# tb-light.net
KiCad netlist of a schematic drawn in EAGLE
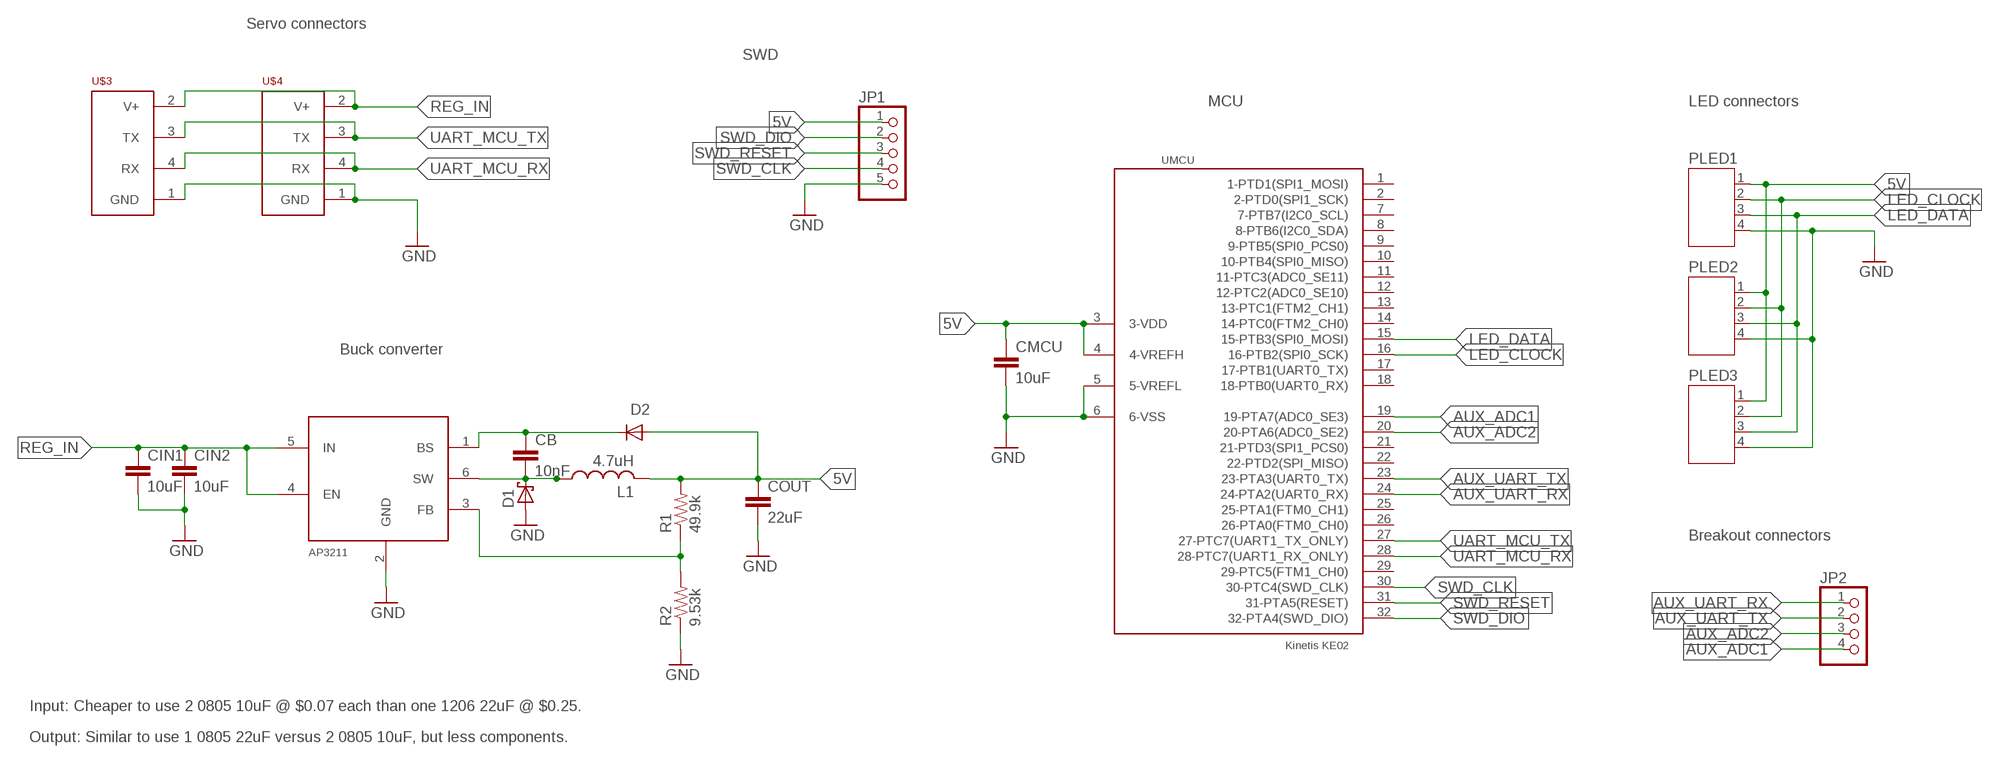
[diagram p0: schematic, sheet 1]

(export (version "E")
  (design (tool "Eeschema 10.0.6"))
  (components
    (comp (ref "CB")
      (value "10nF")
      (footprint "eagle-import:C0805")
      (libsource (lib "eagle-import") (part "CAPACITOR_0805"))
    )
    (comp (ref "CIN1")
      (value "10uF")
      (footprint "eagle-import:C0805")
      (libsource (lib "eagle-import") (part "CAPACITOR_0805"))
    )
    (comp (ref "CIN2")
      (value "10uF")
      (footprint "eagle-import:C0805")
      (libsource (lib "eagle-import") (part "CAPACITOR_0805"))
    )
    (comp (ref "CMCU")
      (value "10uF")
      (footprint "eagle-import:C0805")
      (libsource (lib "eagle-import") (part "CAPACITOR_0805"))
    )
    (comp (ref "COUT")
      (value "22uF")
      (footprint "eagle-import:C0805")
      (libsource (lib "eagle-import") (part "CAPACITOR_0805"))
    )
    (comp (ref "D1")
      (value "SCHOTTKY")
      (footprint "eagle-import:SOD-123FL")
      (libsource (lib "eagle-import") (part "SCHOTTKY"))
    )
    (comp (ref "D2")
      (value "SMALL-SIGNALSOD-123")
      (footprint "eagle-import:SOD-123")
      (libsource (lib "eagle-import") (part "SMALL-SIGNALSOD-123"))
    )
    (comp (ref "JP1")
      (value "PINHD-1X5")
      (footprint "eagle-import:1X05")
      (libsource (lib "eagle-import") (part "PINHD-1X5"))
    )
    (comp (ref "JP2")
      (value "PINHD-1X4")
      (footprint "eagle-import:1X04")
      (libsource (lib "eagle-import") (part "PINHD-1X4"))
    )
    (comp (ref "L1")
      (value "4.7uH")
      (footprint "eagle-import:L_NR6028")
      (libsource (lib "eagle-import") (part "INDUCTOR"))
    )
    (comp (ref "PLED1")
      (value "JST-PH4")
      (footprint "eagle-import:JST-PH4")
      (libsource (lib "eagle-import") (part "JST-PH4"))
    )
    (comp (ref "PLED2")
      (value "JST-PH4")
      (footprint "eagle-import:JST-PH4")
      (libsource (lib "eagle-import") (part "JST-PH4"))
    )
    (comp (ref "PLED3")
      (value "JST-PH4")
      (footprint "eagle-import:JST-PH4")
      (libsource (lib "eagle-import") (part "JST-PH4"))
    )
    (comp (ref "R1")
      (value "49.9k")
      (footprint "eagle-import:R0805")
      (libsource (lib "eagle-import") (part "RESISTOR_0805"))
    )
    (comp (ref "R2")
      (value "9.53k")
      (footprint "eagle-import:R0805")
      (libsource (lib "eagle-import") (part "RESISTOR_0805"))
    )
    (comp (ref "U$3")
      (value "SERVO-CONNVERT")
      (footprint "eagle-import:TE-AMP-4PIN")
      (libsource (lib "eagle-import") (part "SERVO-CONNVERT"))
    )
    (comp (ref "U$4")
      (value "SERVO-CONNVERT")
      (footprint "eagle-import:TE-AMP-4PIN")
      (libsource (lib "eagle-import") (part "SERVO-CONNVERT"))
    )
    (comp (ref "UMCU")
      (value "KE02")
      (footprint "eagle-import:TQFP32-08")
      (libsource (lib "eagle-import") (part "KE02"))
    )
    (comp (ref "UREG")
      (value "AP3211")
      (footprint "eagle-import:SOT23-6")
      (libsource (lib "eagle-import") (part "AP3211"))
    )
  )
  (nets
    (net (code "1") (name "5V") (class "Default")
      (node (ref "CMCU") (pin "1") (pinfunction "1_1") (pintype "passive"))
      (node (ref "COUT") (pin "1") (pinfunction "1_1") (pintype "passive"))
      (node (ref "D2") (pin "A") (pinfunction "A_A") (pintype "passive"))
      (node (ref "JP1") (pin "1") (pinfunction "1_1") (pintype "passive"))
      (node (ref "L1") (pin "P$2") (pinfunction "2_P$2") (pintype "passive"))
      (node (ref "PLED1") (pin "1") (pinfunction "1_1") (pintype "passive"))
      (node (ref "PLED2") (pin "1") (pinfunction "1_1") (pintype "passive"))
      (node (ref "PLED3") (pin "1") (pinfunction "1_1") (pintype "passive"))
      (node (ref "R1") (pin "2") (pinfunction "2_2") (pintype "passive"))
      (node (ref "UMCU") (pin "3") (pinfunction "3-VDD_3") (pintype "bidirectional"))
      (node (ref "UMCU") (pin "4") (pinfunction "4-VREFH_4") (pintype "bidirectional"))
    )
    (net (code "2") (name "AUX_ADC1") (class "Default")
      (node (ref "JP2") (pin "4") (pinfunction "4_4") (pintype "passive"))
      (node (ref "UMCU") (pin "19") (pinfunction "19-PTA7(ADC0_SE3)_19") (pintype "bidirectional"))
    )
    (net (code "3") (name "AUX_ADC2") (class "Default")
      (node (ref "JP2") (pin "3") (pinfunction "3_3") (pintype "passive"))
      (node (ref "UMCU") (pin "20") (pinfunction "20-PTA6(ADC0_SE2)_20") (pintype "bidirectional"))
    )
    (net (code "4") (name "AUX_UART_RX") (class "Default")
      (node (ref "JP2") (pin "1") (pinfunction "1_1") (pintype "passive"))
      (node (ref "UMCU") (pin "24") (pinfunction "24-PTA2(UART0_RX)_24") (pintype "bidirectional"))
    )
    (net (code "5") (name "AUX_UART_TX") (class "Default")
      (node (ref "JP2") (pin "2") (pinfunction "2_2") (pintype "passive"))
      (node (ref "UMCU") (pin "23") (pinfunction "23-PTA3(UART0_TX)_23") (pintype "bidirectional"))
    )
    (net (code "6") (name "GND") (class "Default")
      (node (ref "CIN1") (pin "2") (pinfunction "2_2") (pintype "passive"))
      (node (ref "CIN2") (pin "2") (pinfunction "2_2") (pintype "passive"))
      (node (ref "CMCU") (pin "2") (pinfunction "2_2") (pintype "passive"))
      (node (ref "COUT") (pin "2") (pinfunction "2_2") (pintype "passive"))
      (node (ref "D1") (pin "A") (pinfunction "A_A") (pintype "passive"))
      (node (ref "JP1") (pin "5") (pinfunction "5_5") (pintype "passive"))
      (node (ref "PLED1") (pin "4") (pinfunction "4_4") (pintype "passive"))
      (node (ref "PLED2") (pin "4") (pinfunction "4_4") (pintype "passive"))
      (node (ref "PLED3") (pin "4") (pinfunction "4_4") (pintype "passive"))
      (node (ref "R2") (pin "1") (pinfunction "1_1") (pintype "passive"))
      (node (ref "U$3") (pin "1") (pinfunction "GND_1") (pintype "bidirectional"))
      (node (ref "U$4") (pin "1") (pinfunction "GND_1") (pintype "bidirectional"))
      (node (ref "UMCU") (pin "5") (pinfunction "5-VREFL_5") (pintype "bidirectional"))
      (node (ref "UMCU") (pin "6") (pinfunction "6-VSS_6") (pintype "bidirectional"))
      (node (ref "UREG") (pin "2") (pinfunction "GND_2") (pintype "bidirectional"))
    )
    (net (code "7") (name "LED_CLOCK") (class "Default")
      (node (ref "PLED1") (pin "2") (pinfunction "2_2") (pintype "passive"))
      (node (ref "PLED2") (pin "2") (pinfunction "2_2") (pintype "passive"))
      (node (ref "PLED3") (pin "2") (pinfunction "2_2") (pintype "passive"))
      (node (ref "UMCU") (pin "16") (pinfunction "16-PTB2(SPI0_SCK)_16") (pintype "bidirectional"))
    )
    (net (code "8") (name "LED_DATA") (class "Default")
      (node (ref "PLED1") (pin "3") (pinfunction "3_3") (pintype "passive"))
      (node (ref "PLED2") (pin "3") (pinfunction "3_3") (pintype "passive"))
      (node (ref "PLED3") (pin "3") (pinfunction "3_3") (pintype "passive"))
      (node (ref "UMCU") (pin "15") (pinfunction "15-PTB3(SPI0_MOSI)_15") (pintype "bidirectional"))
    )
    (net (code "9") (name "Net-(L1-1)") (class "Default")
      (node (ref "CB") (pin "2") (pinfunction "2_2") (pintype "passive"))
      (node (ref "D1") (pin "C") (pinfunction "C_C") (pintype "passive"))
      (node (ref "L1") (pin "P$1") (pinfunction "1_P$1") (pintype "passive"))
      (node (ref "UREG") (pin "6") (pinfunction "SW_6") (pintype "bidirectional"))
    )
    (net (code "10") (name "Net-(UREG-BS)") (class "Default")
      (node (ref "CB") (pin "1") (pinfunction "1_1") (pintype "passive"))
      (node (ref "D2") (pin "C") (pinfunction "C_C") (pintype "passive"))
      (node (ref "UREG") (pin "1") (pinfunction "BS_1") (pintype "bidirectional"))
    )
    (net (code "11") (name "Net-(UREG-FB)") (class "Default")
      (node (ref "R1") (pin "1") (pinfunction "1_1") (pintype "passive"))
      (node (ref "R2") (pin "2") (pinfunction "2_2") (pintype "passive"))
      (node (ref "UREG") (pin "3") (pinfunction "FB_3") (pintype "bidirectional"))
    )
    (net (code "12") (name "REG_IN") (class "Default")
      (node (ref "CIN1") (pin "1") (pinfunction "1_1") (pintype "passive"))
      (node (ref "CIN2") (pin "1") (pinfunction "1_1") (pintype "passive"))
      (node (ref "U$3") (pin "2") (pinfunction "V+_2") (pintype "bidirectional"))
      (node (ref "U$4") (pin "2") (pinfunction "V+_2") (pintype "bidirectional"))
      (node (ref "UREG") (pin "4") (pinfunction "EN_4") (pintype "bidirectional"))
      (node (ref "UREG") (pin "5") (pinfunction "IN_5") (pintype "bidirectional"))
    )
    (net (code "13") (name "SWD_CLK") (class "Default")
      (node (ref "JP1") (pin "4") (pinfunction "4_4") (pintype "passive"))
      (node (ref "UMCU") (pin "30") (pinfunction "30-PTC4(SWD_CLK)_30") (pintype "bidirectional"))
    )
    (net (code "14") (name "SWD_DIO") (class "Default")
      (node (ref "JP1") (pin "2") (pinfunction "2_2") (pintype "passive"))
      (node (ref "UMCU") (pin "32") (pinfunction "32-PTA4(SWD_DIO)_32") (pintype "bidirectional"))
    )
    (net (code "15") (name "SWD_RESET") (class "Default")
      (node (ref "JP1") (pin "3") (pinfunction "3_3") (pintype "passive"))
      (node (ref "UMCU") (pin "31") (pinfunction "31-PTA5(RESET)_31") (pintype "bidirectional"))
    )
    (net (code "16") (name "UART_MCU_RX") (class "Default")
      (node (ref "U$3") (pin "4") (pinfunction "RX_4") (pintype "bidirectional"))
      (node (ref "U$4") (pin "4") (pinfunction "RX_4") (pintype "bidirectional"))
      (node (ref "UMCU") (pin "28") (pinfunction "28-PTC7(UART1_RX_ONLY)_28") (pintype "bidirectional"))
    )
    (net (code "17") (name "UART_MCU_TX") (class "Default")
      (node (ref "U$3") (pin "3") (pinfunction "TX_3") (pintype "bidirectional"))
      (node (ref "U$4") (pin "3") (pinfunction "TX_3") (pintype "bidirectional"))
      (node (ref "UMCU") (pin "27") (pinfunction "27-PTC7(UART1_TX_ONLY)_27") (pintype "bidirectional"))
    )
    (net (code "18") (name "unconnected-(UMCU-1-PTD1(SPI1_MOSI)-Pad1)") (class "Default")
      (node (ref "UMCU") (pin "1") (pinfunction "1-PTD1(SPI1_MOSI)_1") (pintype "bidirectional"))
    )
    (net (code "19") (name "unconnected-(UMCU-2-PTD0(SPI1_SCK)-Pad2)") (class "Default")
      (node (ref "UMCU") (pin "2") (pinfunction "2-PTD0(SPI1_SCK)_2") (pintype "bidirectional"))
    )
    (net (code "20") (name "unconnected-(UMCU-7-PTB7(I2C0_SCL)-Pad7)") (class "Default")
      (node (ref "UMCU") (pin "7") (pinfunction "7-PTB7(I2C0_SCL)_7") (pintype "bidirectional"))
    )
    (net (code "21") (name "unconnected-(UMCU-8-PTB6(I2C0_SDA)-Pad8)") (class "Default")
      (node (ref "UMCU") (pin "8") (pinfunction "8-PTB6(I2C0_SDA)_8") (pintype "bidirectional"))
    )
    (net (code "22") (name "unconnected-(UMCU-9-PTB5(SPI0_PCS0)-Pad9)") (class "Default")
      (node (ref "UMCU") (pin "9") (pinfunction "9-PTB5(SPI0_PCS0)_9") (pintype "bidirectional"))
    )
    (net (code "23") (name "unconnected-(UMCU-10-PTB4(SPI0_MISO)-Pad10)") (class "Default")
      (node (ref "UMCU") (pin "10") (pinfunction "10-PTB4(SPI0_MISO)_10") (pintype "bidirectional"))
    )
    (net (code "24") (name "unconnected-(UMCU-11-PTC3(ADC0_SE11)-Pad11)") (class "Default")
      (node (ref "UMCU") (pin "11") (pinfunction "11-PTC3(ADC0_SE11)_11") (pintype "bidirectional"))
    )
    (net (code "25") (name "unconnected-(UMCU-12-PTC2(ADC0_SE10)-Pad12)") (class "Default")
      (node (ref "UMCU") (pin "12") (pinfunction "12-PTC2(ADC0_SE10)_12") (pintype "bidirectional"))
    )
    (net (code "26") (name "unconnected-(UMCU-13-PTC1(FTM2_CH1)-Pad13)") (class "Default")
      (node (ref "UMCU") (pin "13") (pinfunction "13-PTC1(FTM2_CH1)_13") (pintype "bidirectional"))
    )
    (net (code "27") (name "unconnected-(UMCU-14-PTC0(FTM2_CH0)-Pad14)") (class "Default")
      (node (ref "UMCU") (pin "14") (pinfunction "14-PTC0(FTM2_CH0)_14") (pintype "bidirectional"))
    )
    (net (code "28") (name "unconnected-(UMCU-17-PTB1(UART0_TX)-Pad17)") (class "Default")
      (node (ref "UMCU") (pin "17") (pinfunction "17-PTB1(UART0_TX)_17") (pintype "bidirectional"))
    )
    (net (code "29") (name "unconnected-(UMCU-18-PTB0(UART0_RX)-Pad18)") (class "Default")
      (node (ref "UMCU") (pin "18") (pinfunction "18-PTB0(UART0_RX)_18") (pintype "bidirectional"))
    )
    (net (code "30") (name "unconnected-(UMCU-21-PTD3(SPI1_PCS0)-Pad21)") (class "Default")
      (node (ref "UMCU") (pin "21") (pinfunction "21-PTD3(SPI1_PCS0)_21") (pintype "bidirectional"))
    )
    (net (code "31") (name "unconnected-(UMCU-22-PTD2(SPI_MISO)-Pad22)") (class "Default")
      (node (ref "UMCU") (pin "22") (pinfunction "22-PTD2(SPI_MISO)_22") (pintype "bidirectional"))
    )
    (net (code "32") (name "unconnected-(UMCU-25-PTA1(FTM0_CH1)-Pad25)") (class "Default")
      (node (ref "UMCU") (pin "25") (pinfunction "25-PTA1(FTM0_CH1)_25") (pintype "bidirectional"))
    )
    (net (code "33") (name "unconnected-(UMCU-26-PTA0(FTM0_CH0)-Pad26)") (class "Default")
      (node (ref "UMCU") (pin "26") (pinfunction "26-PTA0(FTM0_CH0)_26") (pintype "bidirectional"))
    )
    (net (code "34") (name "unconnected-(UMCU-29-PTC5(FTM1_CH0)-Pad29)") (class "Default")
      (node (ref "UMCU") (pin "29") (pinfunction "29-PTC5(FTM1_CH0)_29") (pintype "bidirectional"))
    )
  )
)
